# 07_-_POWER.net
KiCad netlist of a schematic drawn in Altium Designer
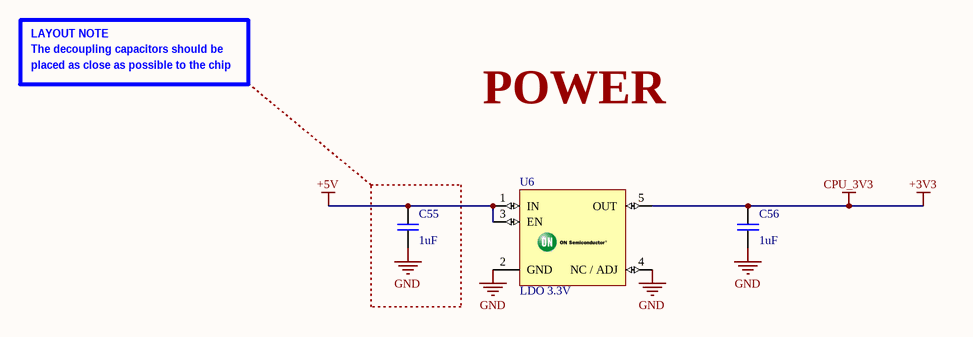
[diagram p0: [07] - POWER.SchDoc]

(export (version "E")
  (design (tool "Eeschema 10.0.6"))
  (components
    (comp (ref "C55")
      (value "1uF")
      (footprint "C0603")
      (description "C0603")
      (fields (field (name "Comment") "02016D104KAT2A"))
      (libsource (lib "Passive components") (part "02016D104KAT2A"))
    )
    (comp (ref "C56")
      (value "1uF")
      (footprint "C0603")
      (description "C0603")
      (fields (field (name "Comment") "02016D104KAT2A"))
      (libsource (lib "Passive components") (part "02016D104KAT2A"))
    )
    (comp (ref "U6")
      (value "LDO 3.3V")
      (footprint "NCV8161BSN330T1G")
      (description "3.3V fixed output LDO, < 10uVrms")
      (libsource (lib "Voltage regulators") (part "NCV8161BSN330T1G"))
    )
  )
  (nets
    (net (code "1") (name "+3V3") (class "Default")
      (node (ref "C56") (pin "2") (pinfunction "2_2") (pintype "passive"))
      (node (ref "U6") (pin "5") (pinfunction "OUT_5") (pintype "bidirectional"))
    )
    (net (code "2") (name "+5V") (class "Default")
      (node (ref "C55") (pin "2") (pinfunction "2_2") (pintype "passive"))
      (node (ref "U6") (pin "1") (pinfunction "IN_1") (pintype "bidirectional"))
      (node (ref "U6") (pin "3") (pinfunction "EN_3") (pintype "bidirectional"))
    )
    (net (code "3") (name "GND") (class "Default")
      (node (ref "C55") (pin "1") (pinfunction "1_1") (pintype "passive"))
      (node (ref "C56") (pin "1") (pinfunction "1_1") (pintype "passive"))
      (node (ref "U6") (pin "2") (pinfunction "GND_2") (pintype "power_in"))
      (node (ref "U6") (pin "4") (pinfunction "NC_/_ADJ_4") (pintype "bidirectional"))
    )
  )
)
